# icetube.net
KiCad netlist of a schematic drawn in EAGLE
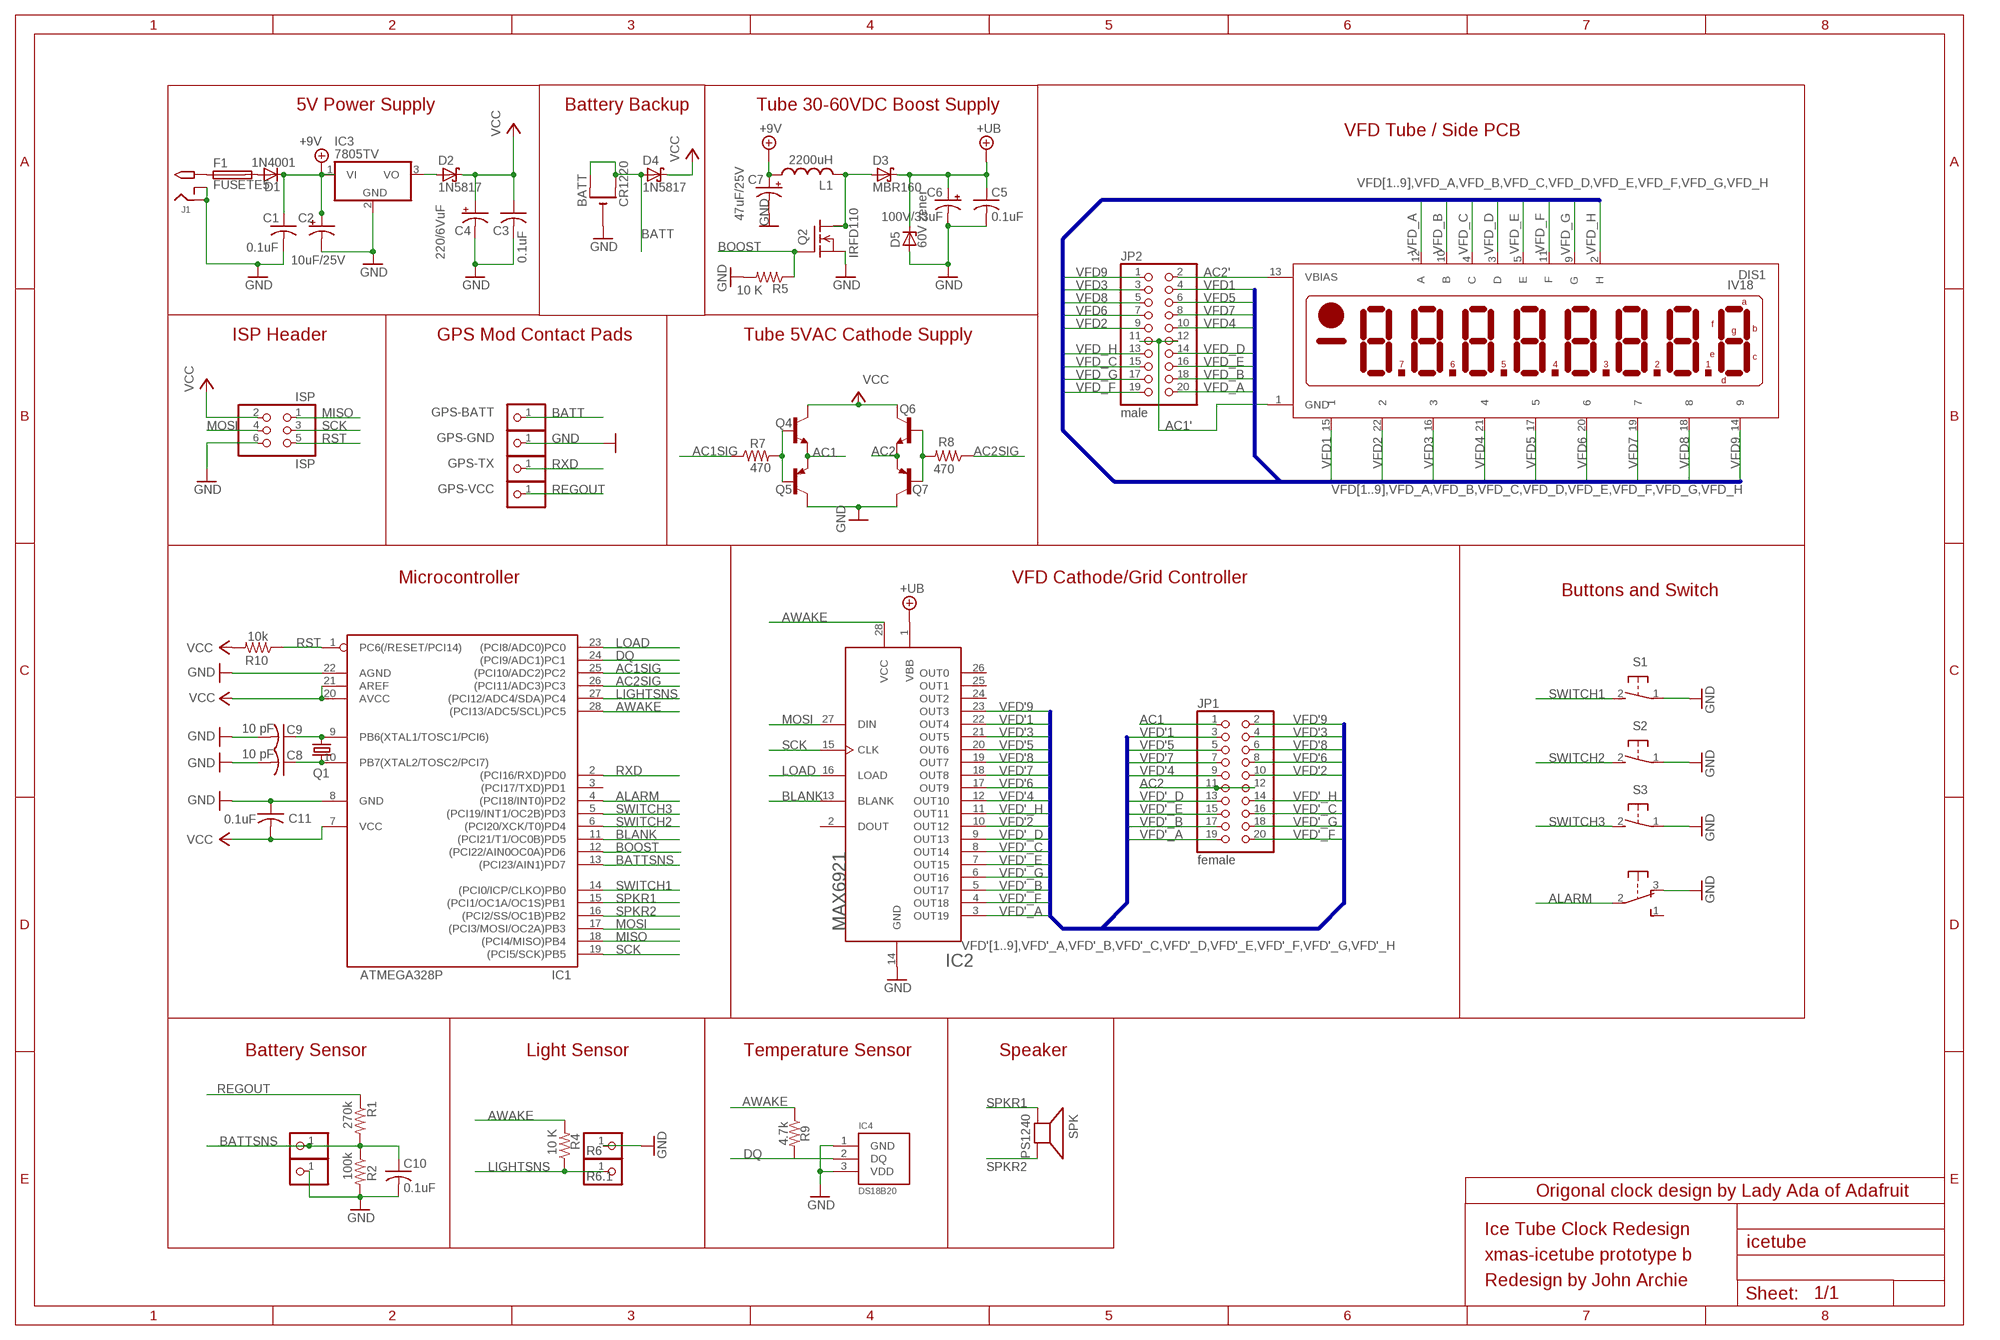
[diagram p0: schematic, sheet 1]

(export (version "E")
  (design (tool "Eeschema 10.0.6"))
  (components
    (comp (ref "BATT")
      (value "CR1220")
      (footprint "eagle-import:CR1220-THM")
      (libsource (lib "eagle-import") (part "CR1220THM"))
    )
    (comp (ref "C1")
      (value "0.1uF")
      (footprint "eagle-import:C025-025X050")
      (libsource (lib "eagle-import") (part "C-US025-025X050"))
    )
    (comp (ref "C2")
      (value "10uF/25V")
      (footprint "eagle-import:E2,5-6")
      (libsource (lib "eagle-import") (part "CPOL-USE2.5-6"))
    )
    (comp (ref "C3")
      (value "0.1uF")
      (footprint "eagle-import:C025-025X050")
      (libsource (lib "eagle-import") (part "C-US025-025X050"))
    )
    (comp (ref "C4")
      (value "220/6VuF")
      (footprint "eagle-import:E2,5-6")
      (libsource (lib "eagle-import") (part "CPOL-USE2.5-6"))
    )
    (comp (ref "C5")
      (value "0.1uF")
      (footprint "eagle-import:C025-024X044")
      (libsource (lib "eagle-import") (part "rcl-ez_C-US025-024X044"))
    )
    (comp (ref "C6")
      (value "100V/33uF")
      (footprint "eagle-import:E3,5-8")
      (libsource (lib "eagle-import") (part "rcl-ez_CPOL-USE3.5-8"))
    )
    (comp (ref "C7")
      (value "47uF/25V")
      (footprint "eagle-import:E2,5-6")
      (libsource (lib "eagle-import") (part "CPOL-USE2.5-6"))
    )
    (comp (ref "C8")
      (value "10 pF")
      (footprint "eagle-import:C025-024X044")
      (libsource (lib "eagle-import") (part "resistor_C-US025-024X044"))
    )
    (comp (ref "C9")
      (value "10 pF")
      (footprint "eagle-import:C025-024X044")
      (libsource (lib "eagle-import") (part "resistor_C-US025-024X044"))
    )
    (comp (ref "C10")
      (value "0.1uF")
      (footprint "eagle-import:C025-024X044")
      (libsource (lib "eagle-import") (part "rcl-ez_C-US025-024X044"))
    )
    (comp (ref "C11")
      (value "0.1uF")
      (footprint "eagle-import:C025-025X050")
      (libsource (lib "eagle-import") (part "C-US025-025X050"))
    )
    (comp (ref "CT2")
      (value "PINHD-1X1")
      (footprint "eagle-import:1X01")
      (libsource (lib "eagle-import") (part "PINHD-1X1"))
    )
    (comp (ref "CT3")
      (value "PINHD-1X1")
      (footprint "eagle-import:1X01")
      (libsource (lib "eagle-import") (part "PINHD-1X1"))
    )
    (comp (ref "D1")
      (value "1N4001")
      (footprint "eagle-import:DO41-10")
      (libsource (lib "eagle-import") (part "1N4004"))
    )
    (comp (ref "D2")
      (value "1N5817")
      (footprint "eagle-import:DO41-10")
      (libsource (lib "eagle-import") (part "SCHOTTKY-DIODEDO41"))
    )
    (comp (ref "D3")
      (value "MBR160")
      (footprint "eagle-import:DO41-10")
      (libsource (lib "eagle-import") (part "SCHOTTKY-DIODEDO41"))
    )
    (comp (ref "D4")
      (value "1N5817")
      (footprint "eagle-import:DO41-10")
      (libsource (lib "eagle-import") (part "SCHOTTKY-DIODEDO41"))
    )
    (comp (ref "D5")
      (value "60V zener")
      (footprint "eagle-import:DO41Z10")
      (libsource (lib "eagle-import") (part "ZENER-DIODEDO41Z10"))
    )
    (comp (ref "DIS1")
      (value "IV18")
      (footprint "eagle-import:IV18")
      (libsource (lib "eagle-import") (part "IV18"))
    )
    (comp (ref "F1")
      (value "FUSETE5")
      (footprint "eagle-import:TE5")
      (libsource (lib "eagle-import") (part "FUSETE5"))
    )
    (comp (ref "GPS-BATT")
      (value "PINHD-1X1")
      (footprint "eagle-import:1X01")
      (libsource (lib "eagle-import") (part "PINHD-1X1"))
    )
    (comp (ref "GPS-GND")
      (value "PINHD-1X1")
      (footprint "eagle-import:1X01")
      (libsource (lib "eagle-import") (part "PINHD-1X1"))
    )
    (comp (ref "GPS-TX")
      (value "PINHD-1X1")
      (footprint "eagle-import:1X01")
      (libsource (lib "eagle-import") (part "PINHD-1X1"))
    )
    (comp (ref "GPS-VCC")
      (value "PINHD-1X1")
      (footprint "eagle-import:1X01")
      (libsource (lib "eagle-import") (part "PINHD-1X1"))
    )
    (comp (ref "IC1")
      (value "ATMEGA328P")
      (footprint "eagle-import:DIL28_3")
      (libsource (lib "eagle-import") (part "ATMEGA168PROUND"))
    )
    (comp (ref "IC2")
      (value "MAX6921")
      (footprint "eagle-import:PLCC-S28")
      (libsource (lib "eagle-import") (part "MAX6921"))
    )
    (comp (ref "IC3")
      (value "7805TV")
      (footprint "eagle-import:TO220V")
      (libsource (lib "eagle-import") (part "78TV05"))
    )
    (comp (ref "IC4")
      (value "DS18B20")
      (footprint "eagle-import:TO92")
      (libsource (lib "eagle-import") (part "DS18B20"))
    )
    (comp (ref "ISP")
      (value "ISP")
      (footprint "eagle-import:2X03")
      (libsource (lib "eagle-import") (part "PINHD-2X3"))
    )
    (comp (ref "J1")
      (value "2.1MMJACK")
      (footprint "eagle-import:PJ-102A")
      (libsource (lib "eagle-import") (part "2.1MMJACK"))
    )
    (comp (ref "JP1")
      (value "female")
      (footprint "eagle-import:2X10")
      (libsource (lib "eagle-import") (part "PINHD-2X10"))
    )
    (comp (ref "JP2")
      (value "male")
      (footprint "eagle-import:2X10")
      (libsource (lib "eagle-import") (part "PINHD-2X10"))
    )
    (comp (ref "L1")
      (value "2200uH")
      (footprint "eagle-import:6000")
      (libsource (lib "eagle-import") (part "L"))
    )
    (comp (ref "Q1")
      (value "32.768 khz")
      (footprint "eagle-import:TC26V")
      (libsource (lib "eagle-import") (part "CRYTALTC26V"))
    )
    (comp (ref "Q2")
      (value "IRFD110")
      (footprint "eagle-import:DIL04")
      (libsource (lib "eagle-import") (part "IRFD110"))
    )
    (comp (ref "Q4")
      (value "-NPN-TO92-EBC")
      (footprint "eagle-import:TO92-EBC")
      (libsource (lib "eagle-import") (part "-NPN-TO92-EBC"))
    )
    (comp (ref "Q5")
      (value "-PNP-TO92-EBC")
      (footprint "eagle-import:TO92-EBC")
      (libsource (lib "eagle-import") (part "-PNP-TO92-EBC"))
    )
    (comp (ref "Q6")
      (value "-NPN-TO92-EBC")
      (footprint "eagle-import:TO92-EBC")
      (libsource (lib "eagle-import") (part "-NPN-TO92-EBC"))
    )
    (comp (ref "Q7")
      (value "-PNP-TO92-EBC")
      (footprint "eagle-import:TO92-EBC")
      (libsource (lib "eagle-import") (part "-PNP-TO92-EBC"))
    )
    (comp (ref "R1")
      (value "270k")
      (footprint "eagle-import:0207_10")
      (libsource (lib "eagle-import") (part "R-US_0207/10"))
    )
    (comp (ref "R2")
      (value "100k")
      (footprint "eagle-import:0207_10")
      (libsource (lib "eagle-import") (part "R-US_0207/10"))
    )
    (comp (ref "R4")
      (value "10 K")
      (footprint "eagle-import:0207_5V")
      (libsource (lib "eagle-import") (part "R-US_0207/5V"))
    )
    (comp (ref "R5")
      (value "10 K")
      (footprint "eagle-import:0207_5V")
      (libsource (lib "eagle-import") (part "R-US_0207/5V"))
    )
    (comp (ref "R6")
      (value "PINHD-1X1")
      (footprint "eagle-import:1X01")
      (libsource (lib "eagle-import") (part "PINHD-1X1"))
    )
    (comp (ref "R6.1")
      (value "PINHD-1X1")
      (footprint "eagle-import:1X01")
      (libsource (lib "eagle-import") (part "PINHD-1X1"))
    )
    (comp (ref "R7")
      (value "470")
      (footprint "eagle-import:0207_5V")
      (libsource (lib "eagle-import") (part "R-US_0207/5V"))
    )
    (comp (ref "R8")
      (value "470")
      (footprint "eagle-import:0207_5V")
      (libsource (lib "eagle-import") (part "R-US_0207/5V"))
    )
    (comp (ref "R9")
      (value "4.7k")
      (footprint "eagle-import:0207_10")
      (libsource (lib "eagle-import") (part "R-US_0207/10"))
    )
    (comp (ref "R10")
      (value "10k")
      (footprint "eagle-import:0207_5V")
      (libsource (lib "eagle-import") (part "R-US_0207/5V"))
    )
    (comp (ref "S1")
      (value "31-XX")
      (footprint "eagle-import:B3F-31XX")
      (libsource (lib "eagle-import") (part "31-XX"))
    )
    (comp (ref "S2")
      (value "31-XX")
      (footprint "eagle-import:B3F-31XX")
      (libsource (lib "eagle-import") (part "31-XX"))
    )
    (comp (ref "S3")
      (value "31-XX")
      (footprint "eagle-import:B3F-31XX")
      (libsource (lib "eagle-import") (part "31-XX"))
    )
    (comp (ref "SPK")
      (value "PS1240")
      (footprint "eagle-import:PS12")
      (libsource (lib "eagle-import") (part "SPEAKER/PS12"))
    )
    (comp (ref "SW1")
      (value "OS102011MA1Q")
      (footprint "eagle-import:OS102011MA1Q")
      (libsource (lib "eagle-import") (part "OS102011MA1Q"))
    )
  )
  (nets
    (net (code "1") (name "+9V") (class "Default")
      (node (ref "C1") (pin "1") (pinfunction "1_1") (pintype "passive"))
      (node (ref "C2") (pin "+") (pinfunction "+_+") (pintype "passive"))
      (node (ref "C7") (pin "+") (pinfunction "+_+") (pintype "passive"))
      (node (ref "D1") (pin "C") (pinfunction "C_C") (pintype "passive"))
      (node (ref "IC3") (pin "1") (pinfunction "VI_1") (pintype "input"))
      (node (ref "L1") (pin "1") (pinfunction "1_1") (pintype "passive"))
    )
    (net (code "2") (name "+UB") (class "Default")
      (node (ref "C5") (pin "1") (pinfunction "1_1") (pintype "passive"))
      (node (ref "C6") (pin "+") (pinfunction "+_+") (pintype "passive"))
      (node (ref "D3") (pin "C") (pinfunction "C_C") (pintype "passive"))
      (node (ref "D5") (pin "C") (pinfunction "C_C") (pintype "passive"))
      (node (ref "IC2") (pin "1") (pinfunction "VBB_1") (pintype "power_in"))
    )
    (net (code "3") (name "/AC1") (class "Default")
      (node (ref "JP1") (pin "1") (pinfunction "1_1") (pintype "passive"))
      (node (ref "Q4") (pin "E") (pinfunction "E_E") (pintype "passive"))
      (node (ref "Q5") (pin "E") (pinfunction "E_E") (pintype "passive"))
    )
    (net (code "4") (name "/AC1'") (class "Default")
      (node (ref "DIS1") (pin "1") (pinfunction "GND_1") (pintype "power_in"))
      (node (ref "JP2") (pin "11") (pinfunction "11_11") (pintype "passive"))
      (node (ref "JP2") (pin "12") (pinfunction "12_12") (pintype "passive"))
    )
    (net (code "5") (name "/AC1SIG") (class "Default")
      (node (ref "IC1") (pin "25") (pinfunction "(PCI10/ADC2)PC2_25") (pintype "bidirectional"))
      (node (ref "R7") (pin "1") (pinfunction "1_1") (pintype "passive"))
    )
    (net (code "6") (name "/AC2") (class "Default")
      (node (ref "JP1") (pin "11") (pinfunction "11_11") (pintype "passive"))
      (node (ref "JP1") (pin "12") (pinfunction "12_12") (pintype "passive"))
      (node (ref "Q6") (pin "E") (pinfunction "E_E") (pintype "passive"))
      (node (ref "Q7") (pin "E") (pinfunction "E_E") (pintype "passive"))
    )
    (net (code "7") (name "/AC2'") (class "Default")
      (node (ref "DIS1") (pin "13") (pinfunction "VBIAS_13") (pintype "power_in"))
      (node (ref "JP2") (pin "2") (pinfunction "2_2") (pintype "passive"))
    )
    (net (code "8") (name "/AC2SIG") (class "Default")
      (node (ref "IC1") (pin "26") (pinfunction "(PCI11/ADC3)PC3_26") (pintype "bidirectional"))
      (node (ref "R8") (pin "1") (pinfunction "1_1") (pintype "passive"))
    )
    (net (code "9") (name "/ALARM") (class "Default")
      (node (ref "IC1") (pin "4") (pinfunction "(PCI18/INT0)PD2_4") (pintype "bidirectional"))
      (node (ref "SW1") (pin "2") (pinfunction "P_2") (pintype "passive"))
    )
    (net (code "10") (name "/AWAKE") (class "Default")
      (node (ref "IC1") (pin "28") (pinfunction "(PCI13/ADC5/SCL)PC5_28") (pintype "bidirectional"))
      (node (ref "IC2") (pin "28") (pinfunction "VCC_28") (pintype "power_in"))
      (node (ref "R4") (pin "2") (pinfunction "2_2") (pintype "passive"))
      (node (ref "R9") (pin "1") (pinfunction "1_1") (pintype "passive"))
    )
    (net (code "11") (name "/BATT") (class "Default")
      (node (ref "BATT") (pin "+1") (pinfunction "+_+1") (pintype "passive"))
      (node (ref "BATT") (pin "+2") (pinfunction "+1_+2") (pintype "passive"))
      (node (ref "D4") (pin "A") (pinfunction "A_A") (pintype "passive"))
      (node (ref "GPS-BATT") (pin "1") (pinfunction "1_1") (pintype "passive"))
    )
    (net (code "12") (name "/BATTSNS") (class "Default")
      (node (ref "C10") (pin "1") (pinfunction "1_1") (pintype "passive"))
      (node (ref "CT2") (pin "1") (pinfunction "1_1") (pintype "passive"))
      (node (ref "IC1") (pin "13") (pinfunction "(PCI23/AIN1)PD7_13") (pintype "bidirectional"))
      (node (ref "R1") (pin "2") (pinfunction "2_2") (pintype "passive"))
      (node (ref "R2") (pin "1") (pinfunction "1_1") (pintype "passive"))
    )
    (net (code "13") (name "/BLANK") (class "Default")
      (node (ref "IC1") (pin "11") (pinfunction "(PCI21/T1/OC0B)PD5_11") (pintype "bidirectional"))
      (node (ref "IC2") (pin "13") (pinfunction "BLANK_13") (pintype "input"))
    )
    (net (code "14") (name "/BOOST") (class "Default")
      (node (ref "IC1") (pin "12") (pinfunction "(PCI22/AIN0OC0A)PD6_12") (pintype "bidirectional"))
      (node (ref "Q2") (pin "3") (pinfunction "G_3") (pintype "passive"))
      (node (ref "R5") (pin "1") (pinfunction "1_1") (pintype "passive"))
    )
    (net (code "15") (name "/DQ") (class "Default")
      (node (ref "IC1") (pin "24") (pinfunction "(PCI9/ADC1)PC1_24") (pintype "bidirectional"))
      (node (ref "IC4") (pin "2") (pinfunction "DQ_2") (pintype "bidirectional"))
      (node (ref "R9") (pin "2") (pinfunction "2_2") (pintype "passive"))
    )
    (net (code "16") (name "/LIGHTSNS") (class "Default")
      (node (ref "IC1") (pin "27") (pinfunction "(PCI12/ADC4/SDA)PC4_27") (pintype "bidirectional"))
      (node (ref "R4") (pin "1") (pinfunction "1_1") (pintype "passive"))
      (node (ref "R6.1") (pin "1") (pinfunction "1_1") (pintype "passive"))
    )
    (net (code "17") (name "/LOAD") (class "Default")
      (node (ref "IC1") (pin "23") (pinfunction "(PCI8/ADC0)PC0_23") (pintype "bidirectional"))
      (node (ref "IC2") (pin "16") (pinfunction "LOAD_16") (pintype "input"))
    )
    (net (code "18") (name "/MISO") (class "Default")
      (node (ref "IC1") (pin "18") (pinfunction "(PCI4/MISO)PB4_18") (pintype "bidirectional"))
      (node (ref "ISP") (pin "1") (pinfunction "1_1") (pintype "passive"))
    )
    (net (code "19") (name "/MOSI") (class "Default")
      (node (ref "IC1") (pin "17") (pinfunction "(PCI3/MOSI/OC2A)PB3_17") (pintype "bidirectional"))
      (node (ref "IC2") (pin "27") (pinfunction "DIN_27") (pintype "input"))
      (node (ref "ISP") (pin "4") (pinfunction "4_4") (pintype "passive"))
    )
    (net (code "20") (name "/REGOUT") (class "Default")
      (node (ref "D2") (pin "A") (pinfunction "A_A") (pintype "passive"))
      (node (ref "GPS-VCC") (pin "1") (pinfunction "1_1") (pintype "passive"))
      (node (ref "IC3") (pin "3") (pinfunction "VO_3") (pintype "passive"))
      (node (ref "R1") (pin "1") (pinfunction "1_1") (pintype "passive"))
    )
    (net (code "21") (name "/RST") (class "Default")
      (node (ref "IC1") (pin "1") (pinfunction "PC6(/RESET/PCI14)_1") (pintype "bidirectional"))
      (node (ref "ISP") (pin "5") (pinfunction "5_5") (pintype "passive"))
      (node (ref "R10") (pin "1") (pinfunction "1_1") (pintype "passive"))
    )
    (net (code "22") (name "/RXD") (class "Default")
      (node (ref "GPS-TX") (pin "1") (pinfunction "1_1") (pintype "passive"))
      (node (ref "IC1") (pin "2") (pinfunction "(PCI16/RXD)PD0_2") (pintype "bidirectional"))
    )
    (net (code "23") (name "/SCK") (class "Default")
      (node (ref "IC1") (pin "19") (pinfunction "(PCI5/SCK)PB5_19") (pintype "bidirectional"))
      (node (ref "IC2") (pin "15") (pinfunction "CLK_15") (pintype "input"))
      (node (ref "ISP") (pin "3") (pinfunction "3_3") (pintype "passive"))
    )
    (net (code "24") (name "/SPKR1") (class "Default")
      (node (ref "IC1") (pin "15") (pinfunction "(PCI1/OC1A/OC1S)PB1_15") (pintype "bidirectional"))
      (node (ref "SPK") (pin "P$1") (pinfunction "+_P$1") (pintype "passive"))
    )
    (net (code "25") (name "/SPKR2") (class "Default")
      (node (ref "IC1") (pin "16") (pinfunction "(PCI2/SS/OC1B)PB2_16") (pintype "bidirectional"))
      (node (ref "SPK") (pin "P$2") (pinfunction "-_P$2") (pintype "passive"))
    )
    (net (code "26") (name "/SWITCH1") (class "Default")
      (node (ref "IC1") (pin "14") (pinfunction "(PCI0/ICP/CLKO)PB0_14") (pintype "bidirectional"))
      (node (ref "S1") (pin "2") (pinfunction "S_2") (pintype "passive"))
    )
    (net (code "27") (name "/SWITCH2") (class "Default")
      (node (ref "IC1") (pin "6") (pinfunction "(PCI20/XCK/T0)PD4_6") (pintype "bidirectional"))
      (node (ref "S2") (pin "2") (pinfunction "S_2") (pintype "passive"))
    )
    (net (code "28") (name "/SWITCH3") (class "Default")
      (node (ref "IC1") (pin "5") (pinfunction "(PCI19/INT1/OC2B)PD3_5") (pintype "bidirectional"))
      (node (ref "S3") (pin "2") (pinfunction "S_2") (pintype "passive"))
    )
    (net (code "29") (name "/VFD'1") (class "Default")
      (node (ref "IC2") (pin "22") (pinfunction "OUT4_22") (pintype "output"))
      (node (ref "JP1") (pin "3") (pinfunction "3_3") (pintype "passive"))
    )
    (net (code "30") (name "/VFD'2") (class "Default")
      (node (ref "IC2") (pin "10") (pinfunction "OUT12_10") (pintype "output"))
      (node (ref "JP1") (pin "10") (pinfunction "10_10") (pintype "passive"))
    )
    (net (code "31") (name "/VFD'3") (class "Default")
      (node (ref "IC2") (pin "21") (pinfunction "OUT5_21") (pintype "output"))
      (node (ref "JP1") (pin "4") (pinfunction "4_4") (pintype "passive"))
    )
    (net (code "32") (name "/VFD'4") (class "Default")
      (node (ref "IC2") (pin "12") (pinfunction "OUT10_12") (pintype "output"))
      (node (ref "JP1") (pin "9") (pinfunction "9_9") (pintype "passive"))
    )
    (net (code "33") (name "/VFD'5") (class "Default")
      (node (ref "IC2") (pin "20") (pinfunction "OUT6_20") (pintype "output"))
      (node (ref "JP1") (pin "5") (pinfunction "5_5") (pintype "passive"))
    )
    (net (code "34") (name "/VFD'6") (class "Default")
      (node (ref "IC2") (pin "17") (pinfunction "OUT9_17") (pintype "output"))
      (node (ref "JP1") (pin "8") (pinfunction "8_8") (pintype "passive"))
    )
    (net (code "35") (name "/VFD'7") (class "Default")
      (node (ref "IC2") (pin "18") (pinfunction "OUT8_18") (pintype "output"))
      (node (ref "JP1") (pin "7") (pinfunction "7_7") (pintype "passive"))
    )
    (net (code "36") (name "/VFD'8") (class "Default")
      (node (ref "IC2") (pin "19") (pinfunction "OUT7_19") (pintype "output"))
      (node (ref "JP1") (pin "6") (pinfunction "6_6") (pintype "passive"))
    )
    (net (code "37") (name "/VFD'9") (class "Default")
      (node (ref "IC2") (pin "23") (pinfunction "OUT3_23") (pintype "output"))
      (node (ref "JP1") (pin "2") (pinfunction "2_2") (pintype "passive"))
    )
    (net (code "38") (name "/VFD'_A") (class "Default")
      (node (ref "IC2") (pin "3") (pinfunction "OUT19_3") (pintype "output"))
      (node (ref "JP1") (pin "19") (pinfunction "19_19") (pintype "passive"))
    )
    (net (code "39") (name "/VFD'_B") (class "Default")
      (node (ref "IC2") (pin "5") (pinfunction "OUT17_5") (pintype "output"))
      (node (ref "JP1") (pin "17") (pinfunction "17_17") (pintype "passive"))
    )
    (net (code "40") (name "/VFD'_C") (class "Default")
      (node (ref "IC2") (pin "8") (pinfunction "OUT14_8") (pintype "output"))
      (node (ref "JP1") (pin "16") (pinfunction "16_16") (pintype "passive"))
    )
    (net (code "41") (name "/VFD'_D") (class "Default")
      (node (ref "IC2") (pin "9") (pinfunction "OUT13_9") (pintype "output"))
      (node (ref "JP1") (pin "13") (pinfunction "13_13") (pintype "passive"))
    )
    (net (code "42") (name "/VFD'_E") (class "Default")
      (node (ref "IC2") (pin "7") (pinfunction "OUT15_7") (pintype "output"))
      (node (ref "JP1") (pin "15") (pinfunction "15_15") (pintype "passive"))
    )
    (net (code "43") (name "/VFD'_F") (class "Default")
      (node (ref "IC2") (pin "4") (pinfunction "OUT18_4") (pintype "output"))
      (node (ref "JP1") (pin "20") (pinfunction "20_20") (pintype "passive"))
    )
    (net (code "44") (name "/VFD'_G") (class "Default")
      (node (ref "IC2") (pin "6") (pinfunction "OUT16_6") (pintype "output"))
      (node (ref "JP1") (pin "18") (pinfunction "18_18") (pintype "passive"))
    )
    (net (code "45") (name "/VFD'_H") (class "Default")
      (node (ref "IC2") (pin "11") (pinfunction "OUT11_11") (pintype "output"))
      (node (ref "JP1") (pin "14") (pinfunction "14_14") (pintype "passive"))
    )
    (net (code "46") (name "/VFD1") (class "Default")
      (node (ref "DIS1") (pin "15") (pinfunction "1_15") (pintype "passive"))
      (node (ref "JP2") (pin "4") (pinfunction "4_4") (pintype "passive"))
    )
    (net (code "47") (name "/VFD2") (class "Default")
      (node (ref "DIS1") (pin "22") (pinfunction "2_22") (pintype "passive"))
      (node (ref "JP2") (pin "9") (pinfunction "9_9") (pintype "passive"))
    )
    (net (code "48") (name "/VFD3") (class "Default")
      (node (ref "DIS1") (pin "16") (pinfunction "3_16") (pintype "passive"))
      (node (ref "JP2") (pin "3") (pinfunction "3_3") (pintype "passive"))
    )
    (net (code "49") (name "/VFD4") (class "Default")
      (node (ref "DIS1") (pin "21") (pinfunction "4_21") (pintype "passive"))
      (node (ref "JP2") (pin "10") (pinfunction "10_10") (pintype "passive"))
    )
    (net (code "50") (name "/VFD5") (class "Default")
      (node (ref "DIS1") (pin "17") (pinfunction "5_17") (pintype "passive"))
      (node (ref "JP2") (pin "6") (pinfunction "6_6") (pintype "passive"))
    )
    (net (code "51") (name "/VFD6") (class "Default")
      (node (ref "DIS1") (pin "20") (pinfunction "6_20") (pintype "passive"))
      (node (ref "JP2") (pin "7") (pinfunction "7_7") (pintype "passive"))
    )
    (net (code "52") (name "/VFD7") (class "Default")
      (node (ref "DIS1") (pin "19") (pinfunction "7_19") (pintype "passive"))
      (node (ref "JP2") (pin "8") (pinfunction "8_8") (pintype "passive"))
    )
    (net (code "53") (name "/VFD8") (class "Default")
      (node (ref "DIS1") (pin "18") (pinfunction "8_18") (pintype "passive"))
      (node (ref "JP2") (pin "5") (pinfunction "5_5") (pintype "passive"))
    )
    (net (code "54") (name "/VFD9") (class "Default")
      (node (ref "DIS1") (pin "14") (pinfunction "9_14") (pintype "passive"))
      (node (ref "JP2") (pin "1") (pinfunction "1_1") (pintype "passive"))
    )
    (net (code "55") (name "/VFD_A") (class "Default")
      (node (ref "DIS1") (pin "12") (pinfunction "A_12") (pintype "passive"))
      (node (ref "JP2") (pin "20") (pinfunction "20_20") (pintype "passive"))
    )
    (net (code "56") (name "/VFD_B") (class "Default")
      (node (ref "DIS1") (pin "10") (pinfunction "B_10") (pintype "passive"))
      (node (ref "JP2") (pin "18") (pinfunction "18_18") (pintype "passive"))
    )
    (net (code "57") (name "/VFD_C") (class "Default")
      (node (ref "DIS1") (pin "4") (pinfunction "C_4") (pintype "passive"))
      (node (ref "JP2") (pin "15") (pinfunction "15_15") (pintype "passive"))
    )
    (net (code "58") (name "/VFD_D") (class "Default")
      (node (ref "DIS1") (pin "3") (pinfunction "D_3") (pintype "passive"))
      (node (ref "JP2") (pin "14") (pinfunction "14_14") (pintype "passive"))
    )
    (net (code "59") (name "/VFD_E") (class "Default")
      (node (ref "DIS1") (pin "5") (pinfunction "E_5") (pintype "passive"))
      (node (ref "JP2") (pin "16") (pinfunction "16_16") (pintype "passive"))
    )
    (net (code "60") (name "/VFD_F") (class "Default")
      (node (ref "DIS1") (pin "11") (pinfunction "F_11") (pintype "passive"))
      (node (ref "JP2") (pin "19") (pinfunction "19_19") (pintype "passive"))
    )
    (net (code "61") (name "/VFD_G") (class "Default")
      (node (ref "DIS1") (pin "9") (pinfunction "G_9") (pintype "passive"))
      (node (ref "JP2") (pin "17") (pinfunction "17_17") (pintype "passive"))
    )
    (net (code "62") (name "/VFD_H") (class "Default")
      (node (ref "DIS1") (pin "2") (pinfunction "H_2") (pintype "passive"))
      (node (ref "JP2") (pin "13") (pinfunction "13_13") (pintype "passive"))
    )
    (net (code "65") (name "GND") (class "Default")
      (node (ref "BATT") (pin "-") (pinfunction "-_-") (pintype "passive"))
      (node (ref "C1") (pin "2") (pinfunction "2_2") (pintype "passive"))
      (node (ref "C10") (pin "2") (pinfunction "2_2") (pintype "passive"))
      (node (ref "C11") (pin "1") (pinfunction "1_1") (pintype "passive"))
      (node (ref "C2") (pin "-") (pinfunction "-_-") (pintype "passive"))
      (node (ref "C3") (pin "2") (pinfunction "2_2") (pintype "passive"))
      (node (ref "C4") (pin "-") (pinfunction "-_-") (pintype "passive"))
      (node (ref "C5") (pin "2") (pinfunction "2_2") (pintype "passive"))
      (node (ref "C6") (pin "-") (pinfunction "-_-") (pintype "passive"))
      (node (ref "C7") (pin "-") (pinfunction "-_-") (pintype "passive"))
      (node (ref "C8") (pin "2") (pinfunction "2_2") (pintype "passive"))
      (node (ref "C9") (pin "2") (pinfunction "2_2") (pintype "passive"))
      (node (ref "CT3") (pin "1") (pinfunction "1_1") (pintype "passive"))
      (node (ref "D5") (pin "A") (pinfunction "A_A") (pintype "passive"))
      (node (ref "GPS-GND") (pin "1") (pinfunction "1_1") (pintype "passive"))
      (node (ref "IC1") (pin "22") (pinfunction "AGND_22") (pintype "bidirectional"))
      (node (ref "IC1") (pin "8") (pinfunction "GND_8") (pintype "bidirectional"))
      (node (ref "IC2") (pin "14") (pinfunction "GND_14") (pintype "power_in"))
      (node (ref "IC3") (pin "2") (pinfunction "GND_2") (pintype "passive"))
      (node (ref "IC4") (pin "1") (pinfunction "GND_1") (pintype "bidirectional"))
      (node (ref "IC4") (pin "3") (pinfunction "VDD_3") (pintype "bidirectional"))
      (node (ref "ISP") (pin "6") (pinfunction "6_6") (pintype "passive"))
      (node (ref "J1") (pin "RING") (pinfunction "RING_RING") (pintype "bidirectional"))
      (node (ref "J1") (pin "RING_SW") (pinfunction "RING_SW_RING_SW") (pintype "bidirectional"))
      (node (ref "Q2") (pin "4") (pinfunction "S_4") (pintype "passive"))
      (node (ref "Q5") (pin "C") (pinfunction "C_C") (pintype "passive"))
      (node (ref "Q7") (pin "C") (pinfunction "C_C") (pintype "passive"))
      (node (ref "R2") (pin "2") (pinfunction "2_2") (pintype "passive"))
      (node (ref "R5") (pin "2") (pinfunction "2_2") (pintype "passive"))
      (node (ref "R6") (pin "1") (pinfunction "1_1") (pintype "passive"))
      (node (ref "S1") (pin "1") (pinfunction "P_1") (pintype "passive"))
      (node (ref "S2") (pin "1") (pinfunction "P_1") (pintype "passive"))
      (node (ref "S3") (pin "1") (pinfunction "P_1") (pintype "passive"))
      (node (ref "SW1") (pin "3") (pinfunction "O_3") (pintype "passive"))
    )
    (net (code "66") (name "Net-(D1-PadA)") (class "Default")
      (node (ref "D1") (pin "A") (pinfunction "A_A") (pintype "passive"))
      (node (ref "F1") (pin "2") (pinfunction "2_2") (pintype "passive"))
    )
    (net (code "67") (name "Net-(F1-Pad1)") (class "Default")
      (node (ref "F1") (pin "1") (pinfunction "1_1") (pintype "passive"))
      (node (ref "J1") (pin "TIP") (pinfunction "TIP_TIP") (pintype "bidirectional"))
    )
    (net (code "68") (name "Net-(IC1-PB6(XTAL1{slash}TOSC1{slash}PCI6))") (class "Default")
      (node (ref "C9") (pin "1") (pinfunction "1_1") (pintype "passive"))
      (node (ref "IC1") (pin "9") (pinfunction "PB6(XTAL1/TOSC1/PCI6)_9") (pintype "bidirectional"))
      (node (ref "Q1") (pin "2") (pinfunction "2_2") (pintype "passive"))
    )
    (net (code "69") (name "Net-(IC1-PB7(XTAL2{slash}TOSC2{slash}PCI7))") (class "Default")
      (node (ref "C8") (pin "1") (pinfunction "1_1") (pintype "passive"))
      (node (ref "IC1") (pin "10") (pinfunction "PB7(XTAL2/TOSC2/PCI7)_10") (pintype "bidirectional"))
      (node (ref "Q1") (pin "1") (pinfunction "1_1") (pintype "passive"))
    )
    (net (code "70") (name "Net-(Q2-D)") (class "Default")
      (node (ref "D3") (pin "A") (pinfunction "A_A") (pintype "passive"))
      (node (ref "L1") (pin "2") (pinfunction "2_2") (pintype "passive"))
      (node (ref "Q2") (pin "1") (pinfunction "D_1") (pintype "passive"))
      (node (ref "Q2") (pin "2") (pinfunction "D1_2") (pintype "passive"))
    )
    (net (code "71") (name "Net-(Q4-PadB)") (class "Default")
      (node (ref "Q4") (pin "B") (pinfunction "B_B") (pintype "passive"))
      (node (ref "Q5") (pin "B") (pinfunction "B_B") (pintype "passive"))
      (node (ref "R7") (pin "2") (pinfunction "2_2") (pintype "passive"))
    )
    (net (code "72") (name "Net-(Q6-PadB)") (class "Default")
      (node (ref "Q6") (pin "B") (pinfunction "B_B") (pintype "passive"))
      (node (ref "Q7") (pin "B") (pinfunction "B_B") (pintype "passive"))
      (node (ref "R8") (pin "2") (pinfunction "2_2") (pintype "passive"))
    )
    (net (code "73") (name "VCC") (class "Default")
      (node (ref "C11") (pin "2") (pinfunction "2_2") (pintype "passive"))
      (node (ref "C3") (pin "1") (pinfunction "1_1") (pintype "passive"))
      (node (ref "C4") (pin "+") (pinfunction "+_+") (pintype "passive"))
      (node (ref "D2") (pin "C") (pinfunction "C_C") (pintype "passive"))
      (node (ref "D4") (pin "C") (pinfunction "C_C") (pintype "passive"))
      (node (ref "IC1") (pin "20") (pinfunction "AVCC_20") (pintype "bidirectional"))
      (node (ref "IC1") (pin "21") (pinfunction "AREF_21") (pintype "bidirectional"))
      (node (ref "IC1") (pin "7") (pinfunction "VCC_7") (pintype "bidirectional"))
      (node (ref "ISP") (pin "2") (pinfunction "2_2") (pintype "passive"))
      (node (ref "Q4") (pin "C") (pinfunction "C_C") (pintype "passive"))
      (node (ref "Q6") (pin "C") (pinfunction "C_C") (pintype "passive"))
      (node (ref "R10") (pin "2") (pinfunction "2_2") (pintype "passive"))
    )
    (net (code "74") (name "unconnected-(IC1-(PCI17{slash}TXD)PD1-Pad3)") (class "Default")
      (node (ref "IC1") (pin "3") (pinfunction "(PCI17/TXD)PD1_3") (pintype "bidirectional"))
    )
    (net (code "75") (name "unconnected-(IC2-DOUT-Pad2)") (class "Default")
      (node (ref "IC2") (pin "2") (pinfunction "DOUT_2") (pintype "output"))
    )
    (net (code "76") (name "unconnected-(IC2-OUT0-Pad26)") (class "Default")
      (node (ref "IC2") (pin "26") (pinfunction "OUT0_26") (pintype "output"))
    )
    (net (code "77") (name "unconnected-(IC2-OUT1-Pad25)") (class "Default")
      (node (ref "IC2") (pin "25") (pinfunction "OUT1_25") (pintype "output"))
    )
    (net (code "78") (name "unconnected-(IC2-OUT2-Pad24)") (class "Default")
      (node (ref "IC2") (pin "24") (pinfunction "OUT2_24") (pintype "output"))
    )
    (net (code "79") (name "unconnected-(SW1A-S-Pad1)") (class "Default")
      (node (ref "SW1") (pin "1") (pinfunction "S_1") (pintype "passive"))
    )
  )
)
